# VibrationMotor.net
KiCad netlist of a schematic drawn in Altium Designer
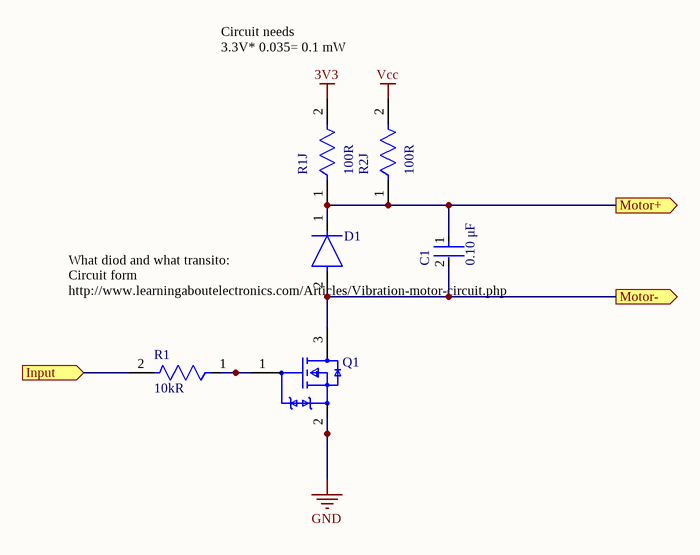
[diagram p0: VibrationMotor.SchDoc]

(export (version "E")
  (design (tool "Eeschema 10.0.6"))
  (components
    (comp (ref "C1")
      (value "0.10 μF")
      (footprint "FP-C0603C-CF-MFG")
      (description "C0603 0.10 μF X7R 30ppm/°C 10.00% 50 V")
      (fields (field (name "TOLERANCE") "0.1"))
      (libsource (lib "Altium Content Vault") (part "b4654b650e69147ec39a6b967a45e02"))
    )
    (comp (ref "D1")
      (value "LS4448GS08")
      (footprint "FP-6_560-5006_01-4-MFG")
      (description "DIODE GEN PURP 100V 300MA SOD80")
      (fields
        (field (name "MANUFACTURER") "Vishay")
        (field (name "OCTOPART") "https://octopart.com/ls4448gs08-vishay-55433966")
      )
      (libsource (lib "Altium Content Vault") (part "d7152d700b627762746794eb795d46e"))
    )
    (comp (ref "Q1")
      (value "DMG2302UK-7")
      (footprint "FP-SOT23-MFG")
      (description "MOSFET N-CH 20V 2.8A SOT23")
      (fields
        (field (name "OCTOPART") "https://octopart.com/dmg2302uk-7-diodes+inc.-73850182")
        (field (name "MANUFACTURER") "Diodes Inc.")
      )
      (libsource (lib "Altium Content Vault") (part "87c0c04a04979492222792dd46c39c9"))
    )
    (comp (ref "R1")
      (value "ESR03EZPJ101")
      (footprint "FP-ESR03-MFG")
      (description "100Ω ±5% 0.25W 0603 Anti-Surge Chip Resistor AEC-Q200")
      (fields (field (name "TOLERANCE") "5%") (field (name "RESISTANCE") "10kR"))
      (libsource (lib "Altium Content Vault") (part "1029c3af85768c4190bb7ad29bc67b5"))
    )
    (comp (ref "R1J")
      (value "ESR03EZPJ101")
      (footprint "FP-ESR03-MFG")
      (description "100Ω ±5% 0.25W 0603 Anti-Surge Chip Resistor AEC-Q200")
      (fields (field (name "TOLERANCE") "5%") (field (name "RESISTANCE") "100R"))
      (libsource (lib "Altium Content Vault") (part "1029c3af85768c4190bb7ad29bc67b5"))
    )
    (comp (ref "R2J")
      (value "ESR03EZPJ101")
      (footprint "FP-ESR03-MFG")
      (description "100Ω ±5% 0.25W 0603 Anti-Surge Chip Resistor AEC-Q200")
      (fields (field (name "TOLERANCE") "5%") (field (name "RESISTANCE") "100R"))
      (libsource (lib "Altium Content Vault") (part "1029c3af85768c4190bb7ad29bc67b5"))
    )
  )
  (nets
    (net (code "1") (name "/Input") (class "Default")
      (node (ref "R1") (pin "2") (pinfunction "2_2") (pintype "passive"))
    )
    (net (code "2") (name "/Motor+") (class "Default")
      (node (ref "C1") (pin "1") (pinfunction "1_1") (pintype "passive"))
      (node (ref "D1") (pin "1") (pinfunction "C_1") (pintype "passive"))
      (node (ref "R1J") (pin "1") (pinfunction "1_1") (pintype "passive"))
      (node (ref "R2J") (pin "1") (pinfunction "1_1") (pintype "passive"))
    )
    (net (code "3") (name "/Motor-") (class "Default")
      (node (ref "C1") (pin "2") (pinfunction "2_2") (pintype "passive"))
      (node (ref "D1") (pin "2") (pinfunction "A_2") (pintype "passive"))
      (node (ref "Q1") (pin "3") (pinfunction "D_3") (pintype "passive"))
    )
    (net (code "4") (name "3V3") (class "Default")
      (node (ref "R1J") (pin "2") (pinfunction "2_2") (pintype "passive"))
    )
    (net (code "5") (name "GND") (class "Default")
      (node (ref "Q1") (pin "2") (pinfunction "S_2") (pintype "passive"))
    )
    (net (code "6") (name "Net-(Q1-G)") (class "Default")
      (node (ref "Q1") (pin "1") (pinfunction "G_1") (pintype "passive"))
      (node (ref "R1") (pin "1") (pinfunction "1_1") (pintype "passive"))
    )
    (net (code "7") (name "Vcc") (class "Default")
      (node (ref "R2J") (pin "2") (pinfunction "2_2") (pintype "passive"))
    )
  )
)
